# Cargador_Lipo_Sencillo_v10.net
KiCad netlist of a schematic drawn in EAGLE
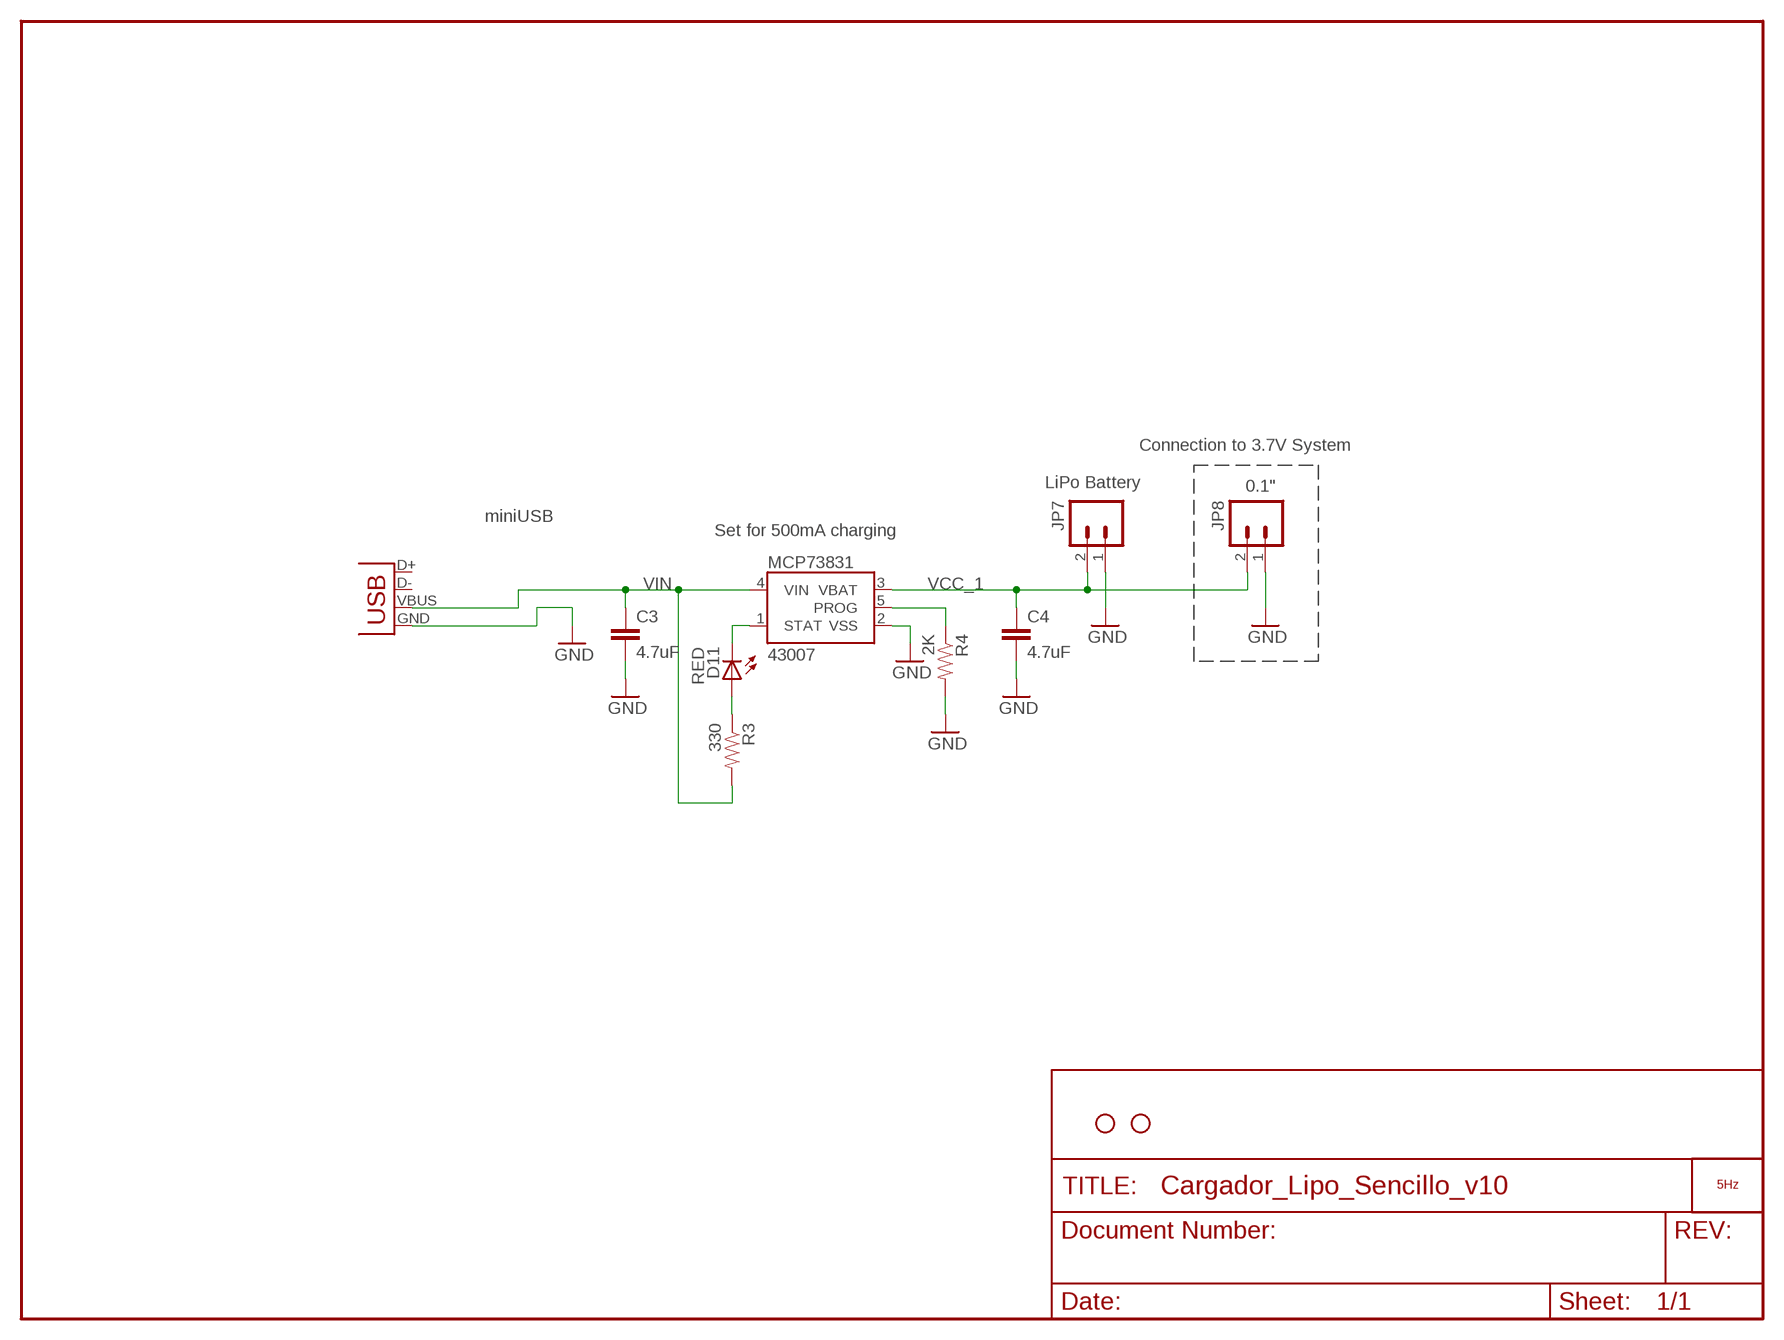
[diagram p0: schematic, sheet 1]

(export (version "E")
  (design (tool "Eeschema 10.0.6"))
  (components
    (comp (ref "C3")
      (value "4.7uF")
      (footprint "eagle-import:0603-CAP")
      (libsource (lib "eagle-import") (part "CAP0603-CAP"))
    )
    (comp (ref "C4")
      (value "4.7uF")
      (footprint "eagle-import:0603-CAP")
      (libsource (lib "eagle-import") (part "CAP0603-CAP"))
    )
    (comp (ref "D11")
      (value "RED")
      (footprint "eagle-import:LED-0603")
      (libsource (lib "eagle-import") (part "LED0603"))
    )
    (comp (ref "JP1")
      (value "STAND-OFF")
      (footprint "eagle-import:STAND-OFF")
      (libsource (lib "eagle-import") (part "STAND-OFF"))
    )
    (comp (ref "JP2")
      (value "STAND-OFF")
      (footprint "eagle-import:STAND-OFF")
      (libsource (lib "eagle-import") (part "STAND-OFF"))
    )
    (comp (ref "JP7")
      (value "LiPo Battery")
      (footprint "eagle-import:JST-2-SMD")
      (libsource (lib "eagle-import") (part "M02-JST-2MM-SMT"))
    )
    (comp (ref "JP8")
      (value "M02POLAR")
      (footprint "eagle-import:MOLEX-1X2")
      (libsource (lib "eagle-import") (part "M02POLAR"))
    )
    (comp (ref "LOGO1")
      (value "LOGO_5HZ_H_10MM")
      (footprint "eagle-import:5HZ_LOGO_H_10MM")
      (libsource (lib "eagle-import") (part "LOGO_5HZ_H_10MM"))
    )
    (comp (ref "MCP73831")
      (value "43007")
      (footprint "eagle-import:SOT23-5")
      (libsource (lib "eagle-import") (part "MCP73831"))
    )
    (comp (ref "R3")
      (value "330")
      (footprint "eagle-import:0603-RES")
      (libsource (lib "eagle-import") (part "RESISTOR0603-RES"))
    )
    (comp (ref "R4")
      (value "2K")
      (footprint "eagle-import:0603-RES")
      (libsource (lib "eagle-import") (part "RESISTOR0603-RES"))
    )
    (comp (ref "X1")
      (value "USBSMD")
      (footprint "eagle-import:USB-MINIB")
      (libsource (lib "eagle-import") (part "USBSMD"))
    )
  )
  (nets
    (net (code "1") (name "/VCC_1") (class "Default")
      (node (ref "C4") (pin "1") (pinfunction "1_1") (pintype "passive"))
      (node (ref "JP7") (pin "2") (pinfunction "2_2") (pintype "passive"))
      (node (ref "JP8") (pin "2") (pinfunction "2_2") (pintype "passive"))
      (node (ref "MCP73831") (pin "3") (pinfunction "VBAT_3") (pintype "power_in"))
    )
    (net (code "2") (name "/VIN") (class "Default")
      (node (ref "C3") (pin "1") (pinfunction "1_1") (pintype "passive"))
      (node (ref "MCP73831") (pin "4") (pinfunction "VIN_4") (pintype "power_in"))
      (node (ref "R3") (pin "2") (pinfunction "2_2") (pintype "passive"))
      (node (ref "X1") (pin "VBUS") (pinfunction "VBUS_VBUS") (pintype "bidirectional"))
    )
    (net (code "3") (name "GND") (class "Default")
      (node (ref "C3") (pin "2") (pinfunction "2_2") (pintype "passive"))
      (node (ref "C4") (pin "2") (pinfunction "2_2") (pintype "passive"))
      (node (ref "JP7") (pin "1") (pinfunction "1_1") (pintype "passive"))
      (node (ref "JP8") (pin "1") (pinfunction "1_1") (pintype "passive"))
      (node (ref "MCP73831") (pin "2") (pinfunction "VSS_2") (pintype "power_in"))
      (node (ref "R4") (pin "2") (pinfunction "2_2") (pintype "passive"))
      (node (ref "X1") (pin "GND") (pinfunction "GND_GND") (pintype "bidirectional"))
    )
    (net (code "4") (name "Net-(D11-PadA)") (class "Default")
      (node (ref "D11") (pin "A") (pinfunction "A_A") (pintype "passive"))
      (node (ref "R3") (pin "1") (pinfunction "1_1") (pintype "passive"))
    )
    (net (code "5") (name "Net-(MCP73831-PROG)") (class "Default")
      (node (ref "MCP73831") (pin "5") (pinfunction "PROG_5") (pintype "input"))
      (node (ref "R4") (pin "1") (pinfunction "1_1") (pintype "passive"))
    )
    (net (code "6") (name "Net-(MCP73831-STAT)") (class "Default")
      (node (ref "D11") (pin "C") (pinfunction "C_C") (pintype "passive"))
      (node (ref "MCP73831") (pin "1") (pinfunction "STAT_1") (pintype "output"))
    )
    (net (code "7") (name "unconnected-(X1-PadD+)") (class "Default")
      (node (ref "X1") (pin "D+") (pinfunction "D+_D+") (pintype "bidirectional"))
    )
    (net (code "8") (name "unconnected-(X1-PadD-)") (class "Default")
      (node (ref "X1") (pin "D-") (pinfunction "D-_D-") (pintype "bidirectional"))
    )
  )
)
